# 6_RK3399_USB2_USIC.net
KiCad netlist of a schematic drawn in Altium Designer
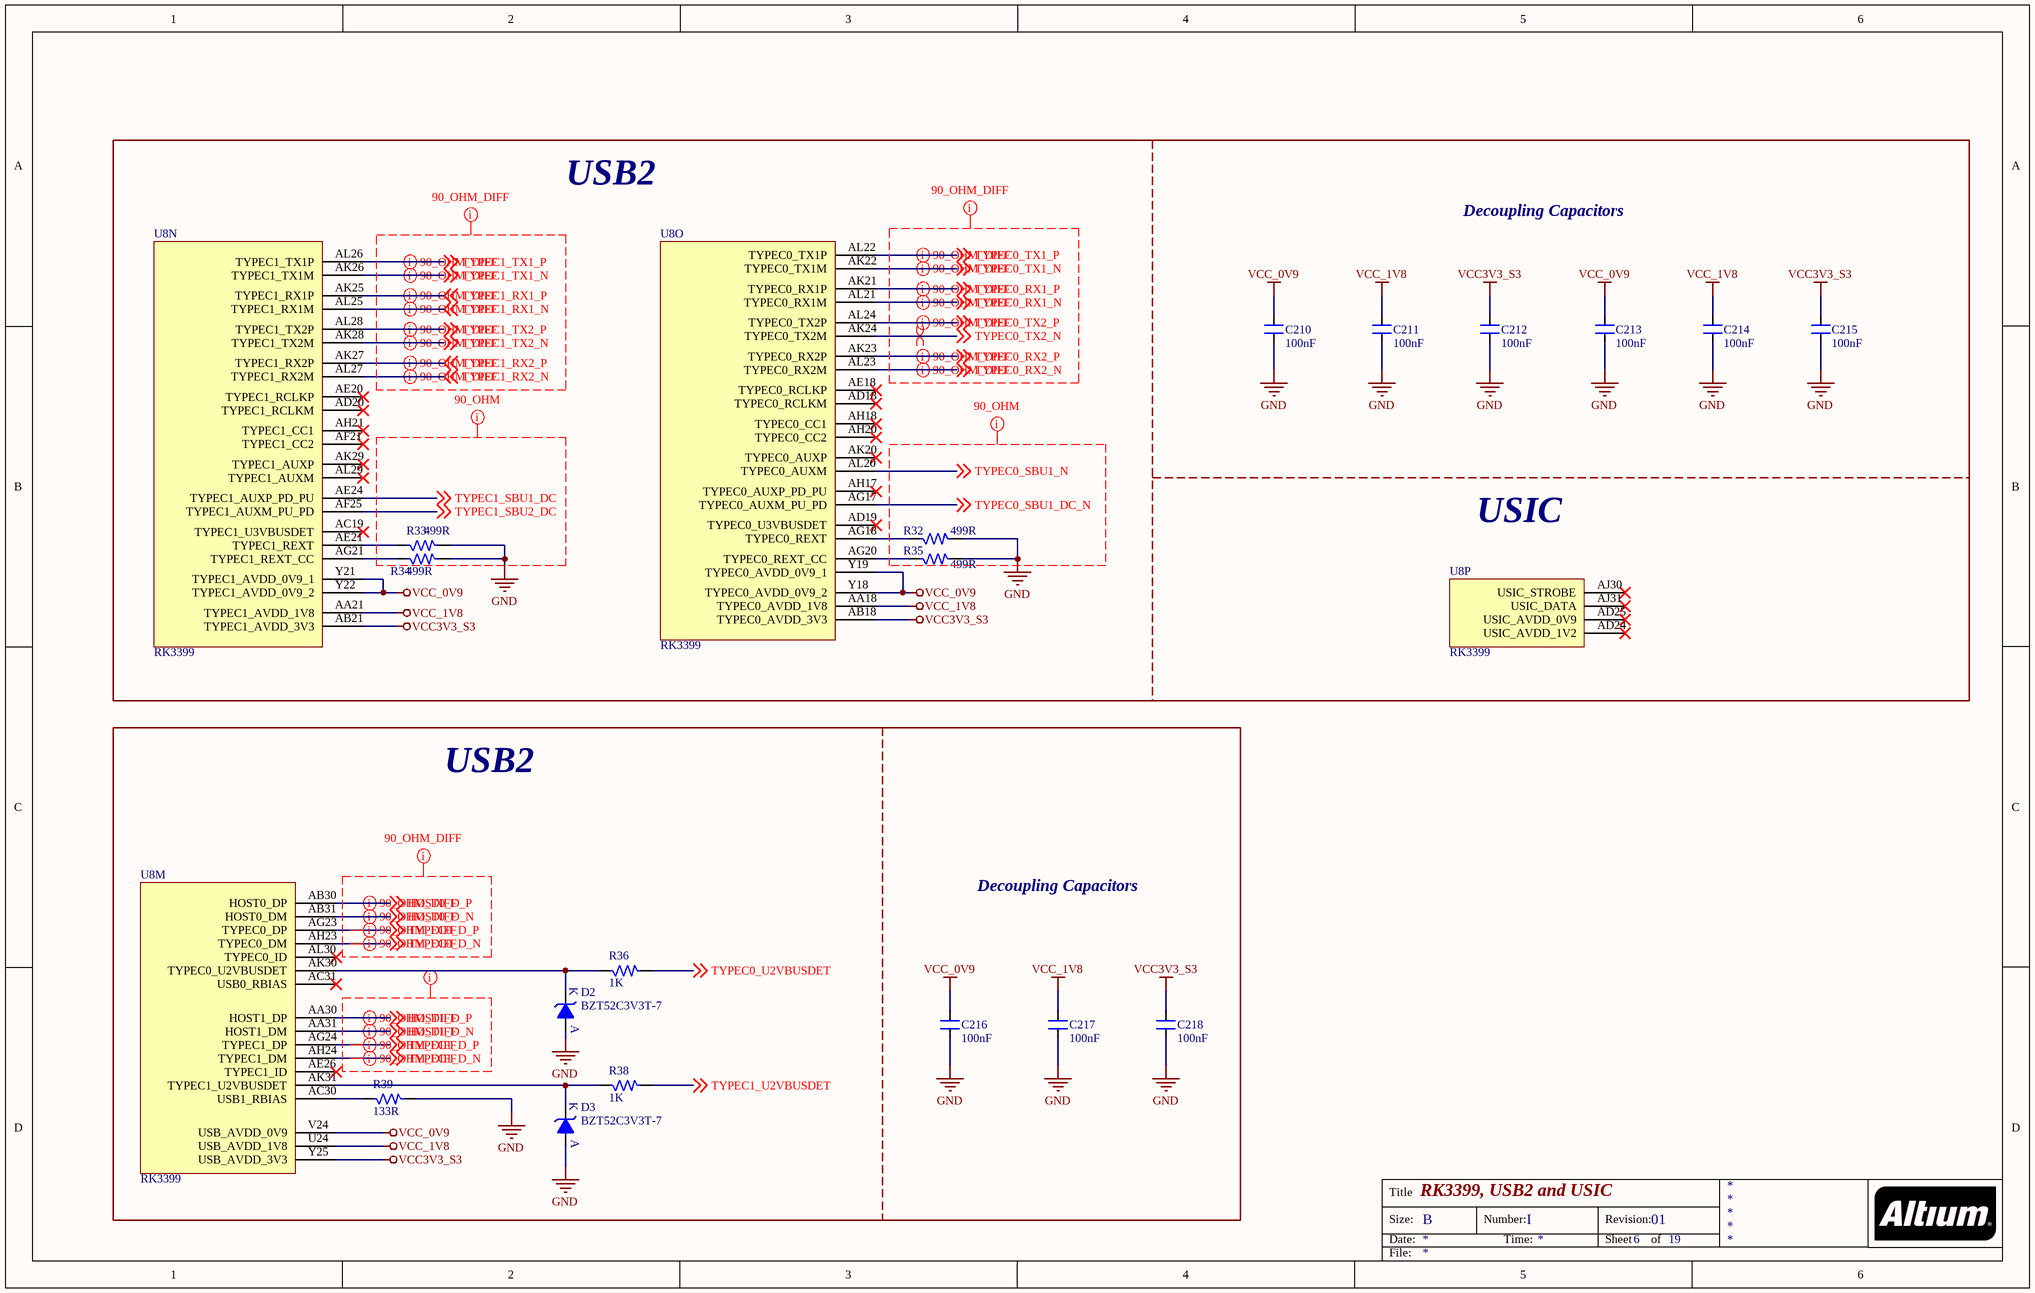
[diagram p0: [6] RK3399_USB2_USIC.SchDoc]

(export (version "E")
  (design (tool "Eeschema 10.0.6"))
  (components
    (comp (ref "C210")
      (value "100nF")
      (footprint "CAP_0201")
      (description "0.1µF ±10% 25V Ceramic Capacitor X5R 0201 (0603 Metric)")
      (fields
        (field (name "MANUFACTURER") "TDK Corporation")
        (field (name "MANUFACTURER PART NUMBER") "C0603X5R1E104K030BB")
      )
      (libsource (lib "EsteemPCB_SOM_Course_intlib") (part "CAP_100nF-25V-10%-0201"))
    )
    (comp (ref "C211")
      (value "100nF")
      (footprint "CAP_0201")
      (description "0.1µF ±10% 25V Ceramic Capacitor X5R 0201 (0603 Metric)")
      (fields
        (field (name "MANUFACTURER") "TDK Corporation")
        (field (name "MANUFACTURER PART NUMBER") "C0603X5R1E104K030BB")
      )
      (libsource (lib "EsteemPCB_SOM_Course_intlib") (part "CAP_100nF-25V-10%-0201"))
    )
    (comp (ref "C212")
      (value "100nF")
      (footprint "CAP_0201")
      (description "0.1µF ±10% 25V Ceramic Capacitor X5R 0201 (0603 Metric)")
      (fields
        (field (name "MANUFACTURER") "TDK Corporation")
        (field (name "MANUFACTURER PART NUMBER") "C0603X5R1E104K030BB")
      )
      (libsource (lib "EsteemPCB_SOM_Course_intlib") (part "CAP_100nF-25V-10%-0201"))
    )
    (comp (ref "C213")
      (value "100nF")
      (footprint "CAP_0201")
      (description "0.1µF ±10% 25V Ceramic Capacitor X5R 0201 (0603 Metric)")
      (fields
        (field (name "MANUFACTURER") "TDK Corporation")
        (field (name "MANUFACTURER PART NUMBER") "C0603X5R1E104K030BB")
      )
      (libsource (lib "EsteemPCB_SOM_Course_intlib") (part "CAP_100nF-25V-10%-0201"))
    )
    (comp (ref "C214")
      (value "100nF")
      (footprint "CAP_0201")
      (description "0.1µF ±10% 25V Ceramic Capacitor X5R 0201 (0603 Metric)")
      (fields
        (field (name "MANUFACTURER") "TDK Corporation")
        (field (name "MANUFACTURER PART NUMBER") "C0603X5R1E104K030BB")
      )
      (libsource (lib "EsteemPCB_SOM_Course_intlib") (part "CAP_100nF-25V-10%-0201"))
    )
    (comp (ref "C215")
      (value "100nF")
      (footprint "CAP_0201")
      (description "0.1µF ±10% 25V Ceramic Capacitor X5R 0201 (0603 Metric)")
      (fields
        (field (name "MANUFACTURER") "TDK Corporation")
        (field (name "MANUFACTURER PART NUMBER") "C0603X5R1E104K030BB")
      )
      (libsource (lib "EsteemPCB_SOM_Course_intlib") (part "CAP_100nF-25V-10%-0201"))
    )
    (comp (ref "C216")
      (value "100nF")
      (footprint "CAP_0201")
      (description "0.1µF ±10% 25V Ceramic Capacitor X5R 0201 (0603 Metric)")
      (fields
        (field (name "MANUFACTURER") "TDK Corporation")
        (field (name "MANUFACTURER PART NUMBER") "C0603X5R1E104K030BB")
      )
      (libsource (lib "EsteemPCB_SOM_Course_intlib") (part "CAP_100nF-25V-10%-0201"))
    )
    (comp (ref "C217")
      (value "100nF")
      (footprint "CAP_0201")
      (description "0.1µF ±10% 25V Ceramic Capacitor X5R 0201 (0603 Metric)")
      (fields
        (field (name "MANUFACTURER") "TDK Corporation")
        (field (name "MANUFACTURER PART NUMBER") "C0603X5R1E104K030BB")
      )
      (libsource (lib "EsteemPCB_SOM_Course_intlib") (part "CAP_100nF-25V-10%-0201"))
    )
    (comp (ref "C218")
      (value "100nF")
      (footprint "CAP_0201")
      (description "0.1µF ±10% 25V Ceramic Capacitor X5R 0201 (0603 Metric)")
      (fields
        (field (name "MANUFACTURER") "TDK Corporation")
        (field (name "MANUFACTURER PART NUMBER") "C0603X5R1E104K030BB")
      )
      (libsource (lib "EsteemPCB_SOM_Course_intlib") (part "CAP_100nF-25V-10%-0201"))
    )
    (comp (ref "D2")
      (value "BZT52C3V3T-7")
      (footprint "DIO_SOD523")
      (description "Zener Diode 3.3V 300mW ±6% Surface Mount SOD-523")
      (fields (field (name "MANUFACTURER") "Diodes Incorporated"))
      (libsource (lib "EsteemPCB_SOM_Course_intlib") (part "DIO-Z_3.3V-300mW-SOD-523"))
    )
    (comp (ref "D3")
      (value "BZT52C3V3T-7")
      (footprint "DIO_SOD523")
      (description "Zener Diode 3.3V 300mW ±6% Surface Mount SOD-523")
      (fields (field (name "MANUFACTURER") "Diodes Incorporated"))
      (libsource (lib "EsteemPCB_SOM_Course_intlib") (part "DIO-Z_3.3V-300mW-SOD-523"))
    )
    (comp (ref "R32")
      (value "499R")
      (footprint "RES_0201")
      (description "499 Ohms ±1% 0.05W, 1/20W Chip Resistor 0201 (0603 Metric) Thick Film")
      (fields
        (field (name "MANUFACTURER") "Stackpole Electronics Inc")
        (field (name "MANUFACTURER PART NUMBER") "RMCF0201FT499R")
      )
      (libsource (lib "EsteemPCB_SOM_Course_intlib") (part "RES_499R-0.05W-1%-0201"))
    )
    (comp (ref "R33")
      (value "499R")
      (footprint "RES_0201")
      (description "499 Ohms ±1% 0.05W, 1/20W Chip Resistor 0201 (0603 Metric) Thick Film")
      (fields
        (field (name "MANUFACTURER") "Stackpole Electronics Inc")
        (field (name "MANUFACTURER PART NUMBER") "RMCF0201FT499R")
      )
      (libsource (lib "EsteemPCB_SOM_Course_intlib") (part "RES_499R-0.05W-1%-0201"))
    )
    (comp (ref "R34")
      (value "499R")
      (footprint "RES_0201")
      (description "499 Ohms ±1% 0.05W, 1/20W Chip Resistor 0201 (0603 Metric) Thick Film")
      (fields
        (field (name "MANUFACTURER") "Stackpole Electronics Inc")
        (field (name "MANUFACTURER PART NUMBER") "RMCF0201FT499R")
      )
      (libsource (lib "EsteemPCB_SOM_Course_intlib") (part "RES_499R-0.05W-1%-0201"))
    )
    (comp (ref "R35")
      (value "499R")
      (footprint "RES_0201")
      (description "499 Ohms ±1% 0.05W, 1/20W Chip Resistor 0201 (0603 Metric) Thick Film")
      (fields
        (field (name "MANUFACTURER") "Stackpole Electronics Inc")
        (field (name "MANUFACTURER PART NUMBER") "RMCF0201FT499R")
      )
      (libsource (lib "EsteemPCB_SOM_Course_intlib") (part "RES_499R-0.05W-1%-0201"))
    )
    (comp (ref "R36")
      (value "1K")
      (footprint "RES_0201")
      (description "1 kOhms ±1% 0.05W, 1/20W Chip Resistor 0201 (0603 Metric) Thick Film")
      (fields
        (field (name "MANUFACTURER") "Yageo")
        (field (name "MANUFACTURER PART NUMBER") "RC0201FR-071KL")
      )
      (libsource (lib "EsteemPCB_SOM_Course_intlib") (part "RES_1K-0.05W-1%-0201"))
    )
    (comp (ref "R38")
      (value "1K")
      (footprint "RES_0201")
      (description "1 kOhms ±1% 0.05W, 1/20W Chip Resistor 0201 (0603 Metric) Thick Film")
      (fields
        (field (name "MANUFACTURER") "Yageo")
        (field (name "MANUFACTURER PART NUMBER") "RC0201FR-071KL")
      )
      (libsource (lib "EsteemPCB_SOM_Course_intlib") (part "RES_1K-0.05W-1%-0201"))
    )
    (comp (ref "R39")
      (value "133R")
      (footprint "RES_0201")
      (description "133 Ohms ±1% 0.05W, 1/20W Chip Resistor 0201 (0603 Metric) Automotive AEC-Q200 Thick Film")
      (fields
        (field (name "MANUFACTURER") "Panasonic Electronic Components")
        (field (name "MANUFACTURER PART NUMBER") "ERJ-1GNF1330C")
      )
      (libsource (lib "EsteemPCB_SOM_Course_intlib") (part "RES_133R-0.05W-1%-0201"))
    )
    (comp (ref "U8")
      (value "RK3399")
      (footprint "FBGA828_23_826X826")
      (description "RK3399 is a low power, high performance processor for computing, personal mobile.")
      (fields (field (name "MANUFACTURER") "Rockchip"))
      (libsource (lib "EsteemPCB_SOM_Course_intlib") (part "IC_RK3399-FCBGA828"))
    )
  )
  (nets
    (net (code "1") (name "GND") (class "Default")
      (node (ref "C210") (pin "1") (pinfunction "1_1") (pintype "passive"))
      (node (ref "C211") (pin "1") (pinfunction "1_1") (pintype "passive"))
      (node (ref "C212") (pin "1") (pinfunction "1_1") (pintype "passive"))
      (node (ref "C213") (pin "1") (pinfunction "1_1") (pintype "passive"))
      (node (ref "C214") (pin "1") (pinfunction "1_1") (pintype "passive"))
      (node (ref "C215") (pin "1") (pinfunction "1_1") (pintype "passive"))
      (node (ref "C216") (pin "1") (pinfunction "1_1") (pintype "passive"))
      (node (ref "C217") (pin "1") (pinfunction "1_1") (pintype "passive"))
      (node (ref "C218") (pin "1") (pinfunction "1_1") (pintype "passive"))
      (node (ref "D2") (pin "A") (pinfunction "A_A") (pintype "passive"))
      (node (ref "D3") (pin "A") (pinfunction "A_A") (pintype "passive"))
      (node (ref "R32") (pin "2") (pinfunction "2_2") (pintype "passive"))
      (node (ref "R33") (pin "2") (pinfunction "2_2") (pintype "passive"))
      (node (ref "R34") (pin "2") (pinfunction "2_2") (pintype "passive"))
      (node (ref "R35") (pin "2") (pinfunction "2_2") (pintype "passive"))
      (node (ref "R39") (pin "2") (pinfunction "2_2") (pintype "passive"))
    )
    (net (code "2") (name "HOST0_D_N") (class "Default")
      (node (ref "U8") (pin "AB31") (pinfunction "HOST0_DM_AB31") (pintype "passive"))
    )
    (net (code "3") (name "HOST0_D_P") (class "Default")
      (node (ref "U8") (pin "AB30") (pinfunction "HOST0_DP_AB30") (pintype "passive"))
    )
    (net (code "4") (name "HOST1_D_N") (class "Default")
      (node (ref "U8") (pin "AA31") (pinfunction "HOST1_DM_AA31") (pintype "passive"))
    )
    (net (code "5") (name "HOST1_D_P") (class "Default")
      (node (ref "U8") (pin "AA30") (pinfunction "HOST1_DP_AA30") (pintype "passive"))
    )
    (net (code "6") (name "Net-(U8M-TYPEC0_U2VBUSDET)") (class "Default")
      (node (ref "D2") (pin "K") (pinfunction "K_K") (pintype "passive"))
      (node (ref "R36") (pin "1") (pinfunction "1_1") (pintype "passive"))
      (node (ref "U8") (pin "AK30") (pinfunction "TYPEC0_U2VBUSDET_AK30") (pintype "passive"))
    )
    (net (code "7") (name "Net-(U8M-TYPEC1_U2VBUSDET)") (class "Default")
      (node (ref "D3") (pin "K") (pinfunction "K_K") (pintype "passive"))
      (node (ref "R38") (pin "1") (pinfunction "1_1") (pintype "passive"))
      (node (ref "U8") (pin "AK31") (pinfunction "TYPEC1_U2VBUSDET_AK31") (pintype "passive"))
    )
    (net (code "8") (name "Net-(U8M-USB1_RBIAS)") (class "Default")
      (node (ref "R39") (pin "1") (pinfunction "1_1") (pintype "passive"))
      (node (ref "U8") (pin "AC30") (pinfunction "USB1_RBIAS_AC30") (pintype "passive"))
    )
    (net (code "9") (name "Net-(U8N-TYPEC1_REXT)") (class "Default")
      (node (ref "R33") (pin "1") (pinfunction "1_1") (pintype "passive"))
      (node (ref "U8") (pin "AE21") (pinfunction "TYPEC1_REXT_AE21") (pintype "passive"))
    )
    (net (code "10") (name "Net-(U8N-TYPEC1_REXT_CC)") (class "Default")
      (node (ref "R34") (pin "1") (pinfunction "1_1") (pintype "passive"))
      (node (ref "U8") (pin "AG21") (pinfunction "TYPEC1_REXT_CC_AG21") (pintype "passive"))
    )
    (net (code "11") (name "Net-(U8O-TYPEC0_REXT)") (class "Default")
      (node (ref "R32") (pin "1") (pinfunction "1_1") (pintype "passive"))
      (node (ref "U8") (pin "AG18") (pinfunction "TYPEC0_REXT_AG18") (pintype "passive"))
    )
    (net (code "12") (name "Net-(U8O-TYPEC0_REXT_CC)") (class "Default")
      (node (ref "R35") (pin "1") (pinfunction "1_1") (pintype "passive"))
      (node (ref "U8") (pin "AG20") (pinfunction "TYPEC0_REXT_CC_AG20") (pintype "passive"))
    )
    (net (code "13") (name "TYPEC0_D_N") (class "Default")
      (node (ref "U8") (pin "AH23") (pinfunction "TYPEC0_DM_AH23") (pintype "passive"))
    )
    (net (code "14") (name "TYPEC0_D_P") (class "Default")
      (node (ref "U8") (pin "AG23") (pinfunction "TYPEC0_DP_AG23") (pintype "passive"))
    )
    (net (code "15") (name "TYPEC0_RX1_N") (class "Default")
      (node (ref "U8") (pin "AL21") (pinfunction "TYPEC0_RX1M_AL21") (pintype "passive"))
    )
    (net (code "16") (name "TYPEC0_RX1_P") (class "Default")
      (node (ref "U8") (pin "AK21") (pinfunction "TYPEC0_RX1P_AK21") (pintype "passive"))
    )
    (net (code "17") (name "TYPEC0_RX2_N") (class "Default")
      (node (ref "U8") (pin "AL23") (pinfunction "TYPEC0_RX2M_AL23") (pintype "passive"))
    )
    (net (code "18") (name "TYPEC0_RX2_P") (class "Default")
      (node (ref "U8") (pin "AK23") (pinfunction "TYPEC0_RX2P_AK23") (pintype "passive"))
    )
    (net (code "19") (name "TYPEC0_SBU1_DC_N") (class "Default")
      (node (ref "U8") (pin "AG17") (pinfunction "TYPEC0_AUXM_PU_PD_AG17") (pintype "passive"))
    )
    (net (code "20") (name "TYPEC0_SBU1_N") (class "Default")
      (node (ref "U8") (pin "AL20") (pinfunction "TYPEC0_AUXM_AL20") (pintype "passive"))
    )
    (net (code "21") (name "TYPEC0_TX1_N") (class "Default")
      (node (ref "U8") (pin "AK22") (pinfunction "TYPEC0_TX1M_AK22") (pintype "passive"))
    )
    (net (code "22") (name "TYPEC0_TX1_P") (class "Default")
      (node (ref "U8") (pin "AL22") (pinfunction "TYPEC0_TX1P_AL22") (pintype "passive"))
    )
    (net (code "23") (name "TYPEC0_TX2_N") (class "Default")
      (node (ref "U8") (pin "AK24") (pinfunction "TYPEC0_TX2M_AK24") (pintype "passive"))
    )
    (net (code "24") (name "TYPEC0_TX2_P") (class "Default")
      (node (ref "U8") (pin "AL24") (pinfunction "TYPEC0_TX2P_AL24") (pintype "passive"))
    )
    (net (code "25") (name "TYPEC0_U2VBUSDET") (class "Default")
      (node (ref "R36") (pin "2") (pinfunction "2_2") (pintype "passive"))
    )
    (net (code "26") (name "TYPEC1_D_N") (class "Default")
      (node (ref "U8") (pin "AH24") (pinfunction "TYPEC1_DM_AH24") (pintype "passive"))
    )
    (net (code "27") (name "TYPEC1_D_P") (class "Default")
      (node (ref "U8") (pin "AG24") (pinfunction "TYPEC1_DP_AG24") (pintype "passive"))
    )
    (net (code "28") (name "TYPEC1_RX1_N") (class "Default")
      (node (ref "U8") (pin "AL25") (pinfunction "TYPEC1_RX1M_AL25") (pintype "passive"))
    )
    (net (code "29") (name "TYPEC1_RX1_P") (class "Default")
      (node (ref "U8") (pin "AK25") (pinfunction "TYPEC1_RX1P_AK25") (pintype "passive"))
    )
    (net (code "30") (name "TYPEC1_RX2_N") (class "Default")
      (node (ref "U8") (pin "AL27") (pinfunction "TYPEC1_RX2M_AL27") (pintype "passive"))
    )
    (net (code "31") (name "TYPEC1_RX2_P") (class "Default")
      (node (ref "U8") (pin "AK27") (pinfunction "TYPEC1_RX2P_AK27") (pintype "passive"))
    )
    (net (code "32") (name "TYPEC1_SBU1_DC") (class "Default")
      (node (ref "U8") (pin "AE24") (pinfunction "TYPEC1_AUXP_PD_PU_AE24") (pintype "passive"))
    )
    (net (code "33") (name "TYPEC1_SBU2_DC") (class "Default")
      (node (ref "U8") (pin "AF25") (pinfunction "TYPEC1_AUXM_PU_PD_AF25") (pintype "passive"))
    )
    (net (code "34") (name "TYPEC1_TX1_N") (class "Default")
      (node (ref "U8") (pin "AK26") (pinfunction "TYPEC1_TX1M_AK26") (pintype "passive"))
    )
    (net (code "35") (name "TYPEC1_TX1_P") (class "Default")
      (node (ref "U8") (pin "AL26") (pinfunction "TYPEC1_TX1P_AL26") (pintype "passive"))
    )
    (net (code "36") (name "TYPEC1_TX2_N") (class "Default")
      (node (ref "U8") (pin "AK28") (pinfunction "TYPEC1_TX2M_AK28") (pintype "passive"))
    )
    (net (code "37") (name "TYPEC1_TX2_P") (class "Default")
      (node (ref "U8") (pin "AL28") (pinfunction "TYPEC1_TX2P_AL28") (pintype "passive"))
    )
    (net (code "38") (name "TYPEC1_U2VBUSDET") (class "Default")
      (node (ref "R38") (pin "2") (pinfunction "2_2") (pintype "passive"))
    )
    (net (code "39") (name "VCC3V3_S3") (class "Default")
      (node (ref "C212") (pin "2") (pinfunction "2_2") (pintype "passive"))
      (node (ref "C215") (pin "2") (pinfunction "2_2") (pintype "passive"))
      (node (ref "C218") (pin "2") (pinfunction "2_2") (pintype "passive"))
      (node (ref "U8") (pin "AB18") (pinfunction "TYPEC0_AVDD_3V3_AB18") (pintype "passive"))
      (node (ref "U8") (pin "AB21") (pinfunction "TYPEC1_AVDD_3V3_AB21") (pintype "passive"))
      (node (ref "U8") (pin "Y25") (pinfunction "USB_AVDD_3V3_Y25") (pintype "passive"))
    )
    (net (code "40") (name "VCC_0V9") (class "Default")
      (node (ref "C210") (pin "2") (pinfunction "2_2") (pintype "passive"))
      (node (ref "C213") (pin "2") (pinfunction "2_2") (pintype "passive"))
      (node (ref "C216") (pin "2") (pinfunction "2_2") (pintype "passive"))
      (node (ref "U8") (pin "V24") (pinfunction "USB_AVDD_0V9_V24") (pintype "passive"))
      (node (ref "U8") (pin "Y18") (pinfunction "TYPEC0_AVDD_0V9_2_Y18") (pintype "passive"))
      (node (ref "U8") (pin "Y19") (pinfunction "TYPEC0_AVDD_0V9_1_Y19") (pintype "passive"))
      (node (ref "U8") (pin "Y21") (pinfunction "TYPEC1_AVDD_0V9_1_Y21") (pintype "passive"))
      (node (ref "U8") (pin "Y22") (pinfunction "TYPEC1_AVDD_0V9_2_Y22") (pintype "passive"))
    )
    (net (code "41") (name "VCC_1V8") (class "Default")
      (node (ref "C211") (pin "2") (pinfunction "2_2") (pintype "passive"))
      (node (ref "C214") (pin "2") (pinfunction "2_2") (pintype "passive"))
      (node (ref "C217") (pin "2") (pinfunction "2_2") (pintype "passive"))
      (node (ref "U8") (pin "AA18") (pinfunction "TYPEC0_AVDD_1V8_AA18") (pintype "passive"))
      (node (ref "U8") (pin "AA21") (pinfunction "TYPEC1_AVDD_1V8_AA21") (pintype "passive"))
      (node (ref "U8") (pin "U24") (pinfunction "USB_AVDD_1V8_U24") (pintype "passive"))
    )
    (net (code "42") (name "unconnected-(U8M-TYPEC0_ID-PadAL30)") (class "Default")
      (node (ref "U8") (pin "AL30") (pinfunction "TYPEC0_ID_AL30") (pintype "passive+no_connect"))
    )
    (net (code "43") (name "unconnected-(U8M-TYPEC1_ID-PadAE26)") (class "Default")
      (node (ref "U8") (pin "AE26") (pinfunction "TYPEC1_ID_AE26") (pintype "passive+no_connect"))
    )
    (net (code "44") (name "unconnected-(U8M-USB0_RBIAS-PadAC31)") (class "Default")
      (node (ref "U8") (pin "AC31") (pinfunction "USB0_RBIAS_AC31") (pintype "passive+no_connect"))
    )
    (net (code "45") (name "unconnected-(U8N-TYPEC1_AUXM-PadAL29)") (class "Default")
      (node (ref "U8") (pin "AL29") (pinfunction "TYPEC1_AUXM_AL29") (pintype "passive+no_connect"))
    )
    (net (code "46") (name "unconnected-(U8N-TYPEC1_AUXP-PadAK29)") (class "Default")
      (node (ref "U8") (pin "AK29") (pinfunction "TYPEC1_AUXP_AK29") (pintype "passive+no_connect"))
    )
    (net (code "47") (name "unconnected-(U8N-TYPEC1_CC1-PadAH21)") (class "Default")
      (node (ref "U8") (pin "AH21") (pinfunction "TYPEC1_CC1_AH21") (pintype "passive+no_connect"))
    )
    (net (code "48") (name "unconnected-(U8N-TYPEC1_CC2-PadAF21)") (class "Default")
      (node (ref "U8") (pin "AF21") (pinfunction "TYPEC1_CC2_AF21") (pintype "passive+no_connect"))
    )
    (net (code "49") (name "unconnected-(U8N-TYPEC1_RCLKM-PadAD20)") (class "Default")
      (node (ref "U8") (pin "AD20") (pinfunction "TYPEC1_RCLKM_AD20") (pintype "passive+no_connect"))
    )
    (net (code "50") (name "unconnected-(U8N-TYPEC1_RCLKP-PadAE20)") (class "Default")
      (node (ref "U8") (pin "AE20") (pinfunction "TYPEC1_RCLKP_AE20") (pintype "passive+no_connect"))
    )
    (net (code "51") (name "unconnected-(U8N-TYPEC1_U3VBUSDET-PadAC19)") (class "Default")
      (node (ref "U8") (pin "AC19") (pinfunction "TYPEC1_U3VBUSDET_AC19") (pintype "passive+no_connect"))
    )
    (net (code "52") (name "unconnected-(U8O-TYPEC0_AUXP-PadAK20)") (class "Default")
      (node (ref "U8") (pin "AK20") (pinfunction "TYPEC0_AUXP_AK20") (pintype "passive+no_connect"))
    )
    (net (code "53") (name "unconnected-(U8O-TYPEC0_AUXP_PD_PU-PadAH17)") (class "Default")
      (node (ref "U8") (pin "AH17") (pinfunction "TYPEC0_AUXP_PD_PU_AH17") (pintype "passive+no_connect"))
    )
    (net (code "54") (name "unconnected-(U8O-TYPEC0_CC1-PadAH18)") (class "Default")
      (node (ref "U8") (pin "AH18") (pinfunction "TYPEC0_CC1_AH18") (pintype "passive+no_connect"))
    )
    (net (code "55") (name "unconnected-(U8O-TYPEC0_CC2-PadAH20)") (class "Default")
      (node (ref "U8") (pin "AH20") (pinfunction "TYPEC0_CC2_AH20") (pintype "passive+no_connect"))
    )
    (net (code "56") (name "unconnected-(U8O-TYPEC0_RCLKM-PadAD18)") (class "Default")
      (node (ref "U8") (pin "AD18") (pinfunction "TYPEC0_RCLKM_AD18") (pintype "passive+no_connect"))
    )
    (net (code "57") (name "unconnected-(U8O-TYPEC0_RCLKP-PadAE18)") (class "Default")
      (node (ref "U8") (pin "AE18") (pinfunction "TYPEC0_RCLKP_AE18") (pintype "passive+no_connect"))
    )
    (net (code "58") (name "unconnected-(U8O-TYPEC0_U3VBUSDET-PadAD19)") (class "Default")
      (node (ref "U8") (pin "AD19") (pinfunction "TYPEC0_U3VBUSDET_AD19") (pintype "passive+no_connect"))
    )
    (net (code "59") (name "unconnected-(U8P-USIC_AVDD_0V9-PadAD25)") (class "Default")
      (node (ref "U8") (pin "AD25") (pinfunction "USIC_AVDD_0V9_AD25") (pintype "passive+no_connect"))
    )
    (net (code "60") (name "unconnected-(U8P-USIC_AVDD_1V2-PadAD24)") (class "Default")
      (node (ref "U8") (pin "AD24") (pinfunction "USIC_AVDD_1V2_AD24") (pintype "passive+no_connect"))
    )
    (net (code "61") (name "unconnected-(U8P-USIC_DATA-PadAJ31)") (class "Default")
      (node (ref "U8") (pin "AJ31") (pinfunction "USIC_DATA_AJ31") (pintype "passive+no_connect"))
    )
    (net (code "62") (name "unconnected-(U8P-USIC_STROBE-PadAJ30)") (class "Default")
      (node (ref "U8") (pin "AJ30") (pinfunction "USIC_STROBE_AJ30") (pintype "passive+no_connect"))
    )
  )
)
